# WirelessStepperMotorController.net
KiCad netlist of a schematic drawn in Altium Designer
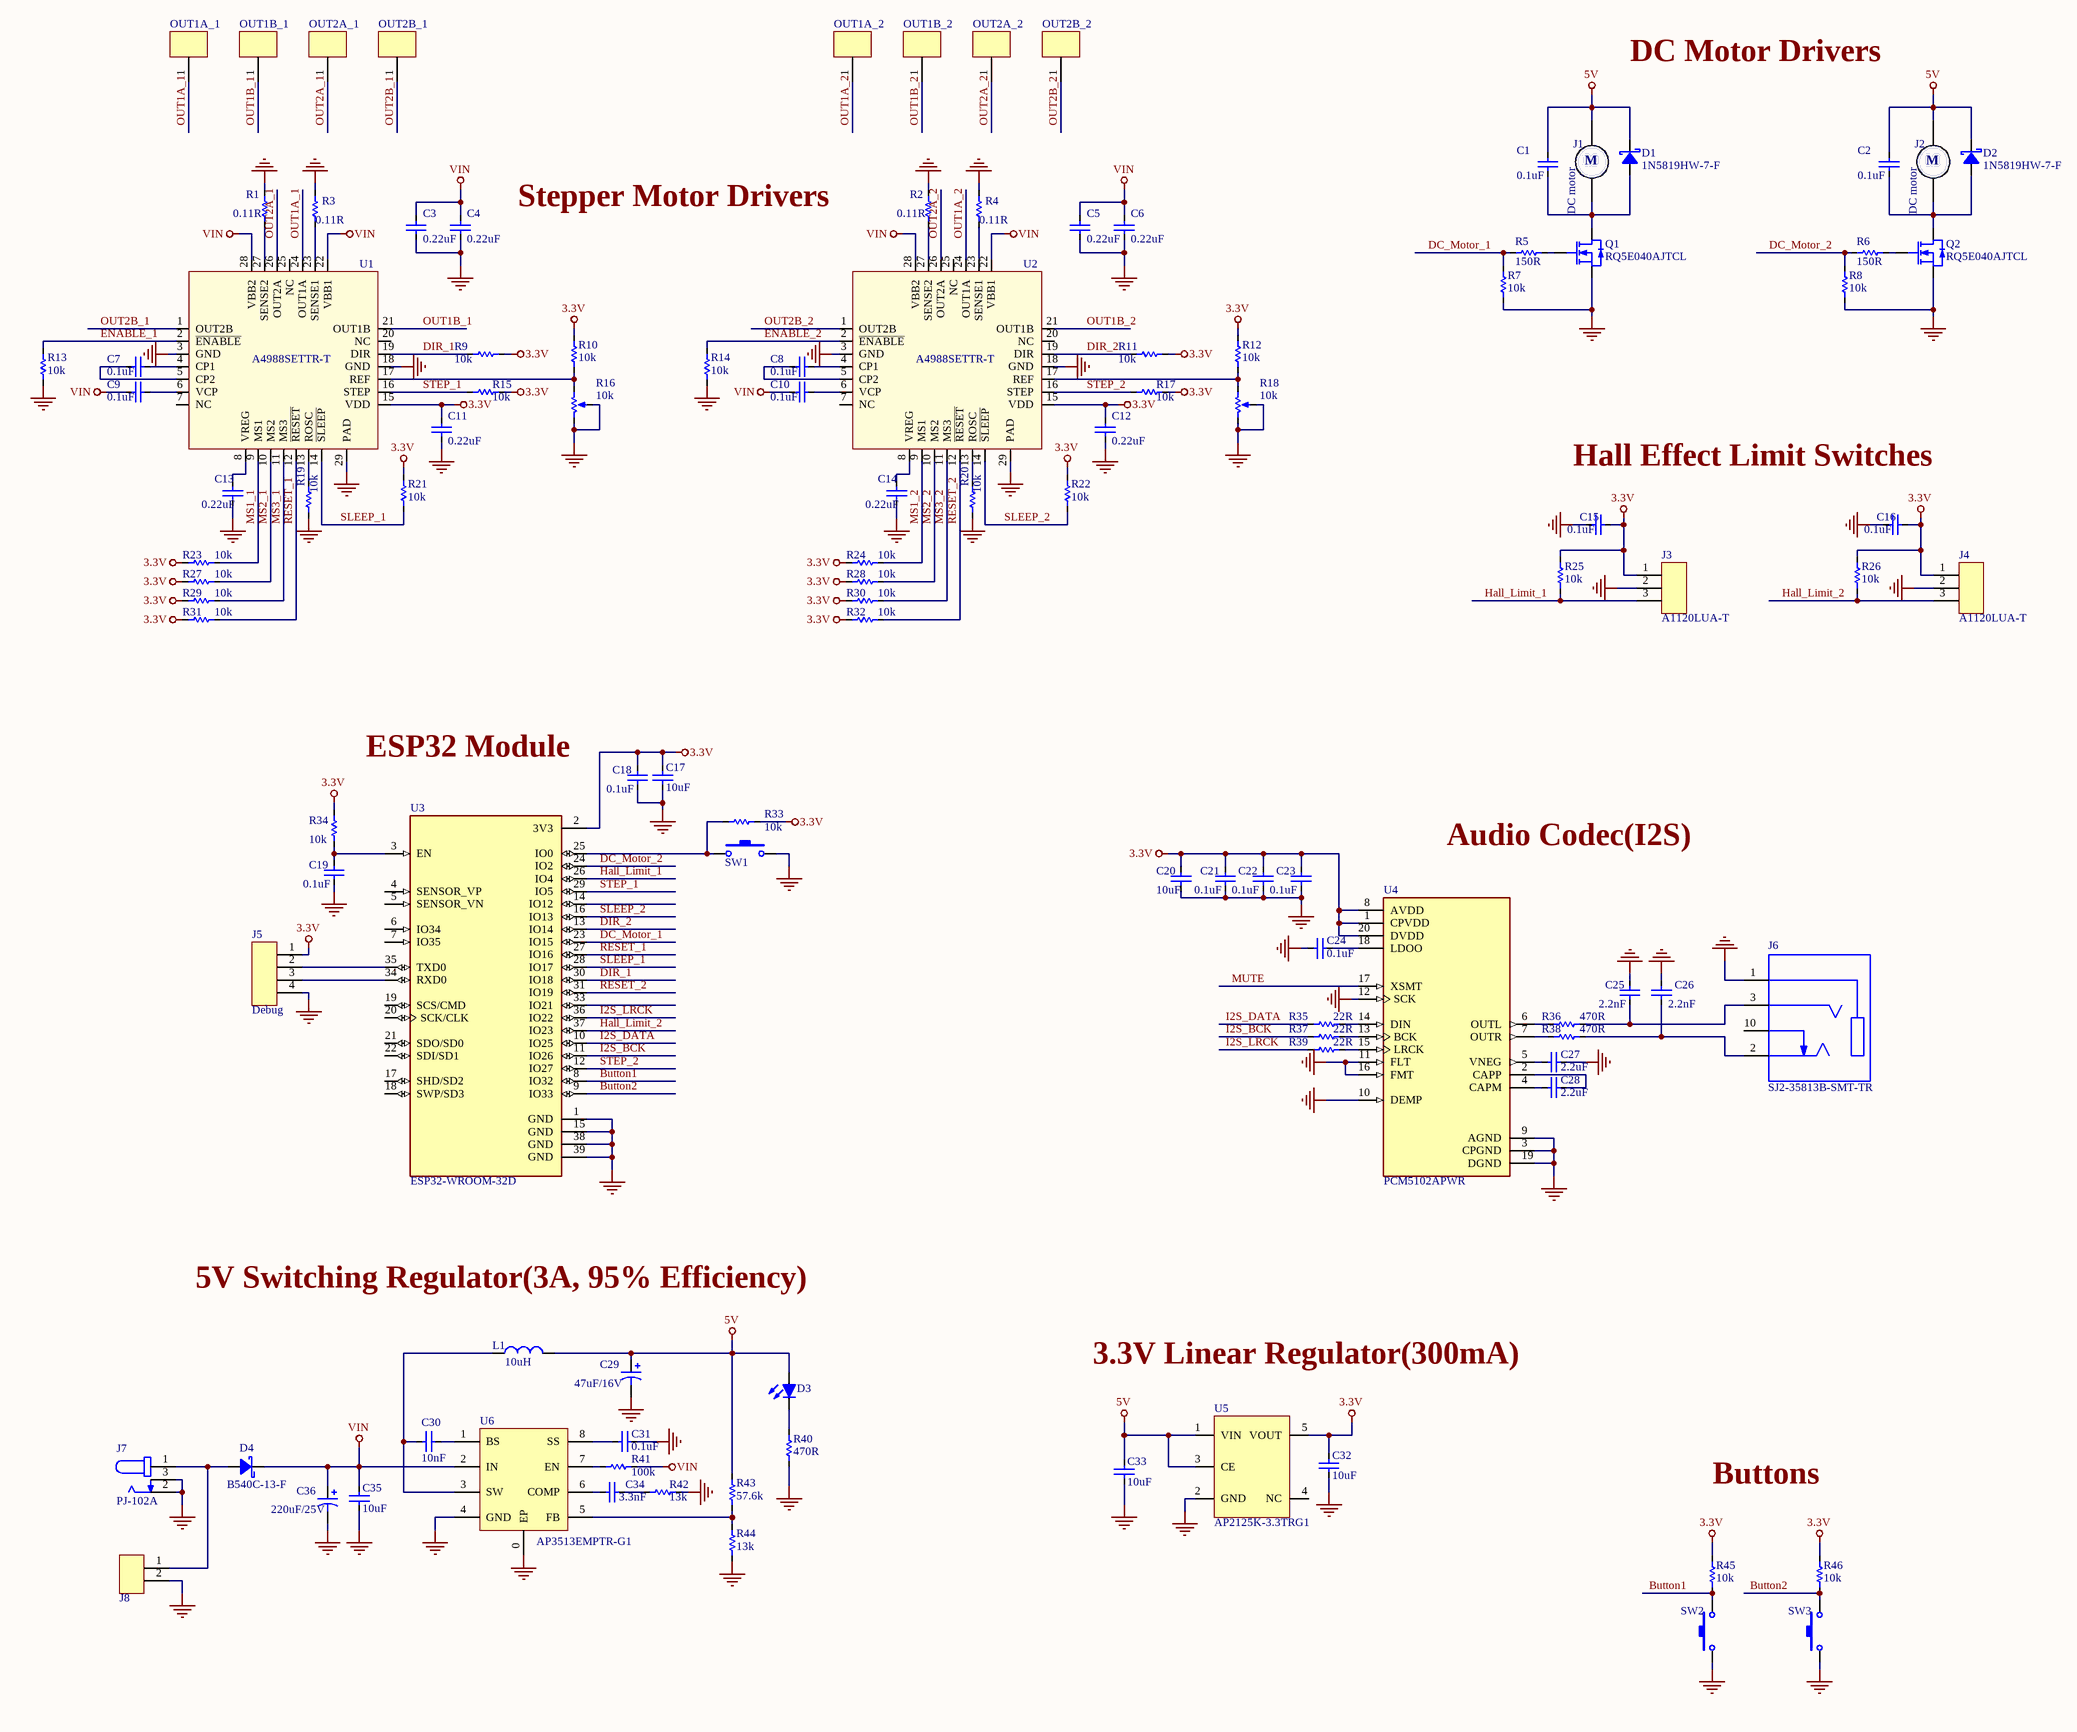
[diagram p0: WirelessStepperMotorController.SchDoc]

(export (version "E")
  (design (tool "Eeschema 10.0.6"))
  (components
    (comp (ref "C1")
      (value "0.1uF")
      (footprint "SMD_C(0603)")
      (description "0.1µF ±10% 25V")
      (fields
        (field (name "MANUFACTURER") "Yageo")
        (field (name "MANUFACTURER PART NUMBER") "CC0603KRX7R8BB104")
      )
      (libsource (lib "Miscellaneous Devices") (part "Cap"))
    )
    (comp (ref "C2")
      (value "0.1uF")
      (footprint "SMD_C(0603)")
      (description "0.1µF ±10% 25V")
      (fields
        (field (name "MANUFACTURER") "Yageo")
        (field (name "MANUFACTURER PART NUMBER") "CC0603KRX7R8BB104")
      )
      (libsource (lib "Miscellaneous Devices") (part "Cap"))
    )
    (comp (ref "C3")
      (value "0.22uF")
      (footprint "SMD_C(0603)")
      (description "0.22µF ±10% 25V")
      (fields
        (field (name "MANUFACTURER") "Yageo")
        (field (name "MANUFACTURER PART NUMBER") "CC0603KRX7R8BB224")
      )
      (libsource (lib "Miscellaneous Devices") (part "Cap"))
    )
    (comp (ref "C4")
      (value "0.22uF")
      (footprint "SMD_C(0603)")
      (description "0.22µF ±10% 25V")
      (fields
        (field (name "MANUFACTURER") "Yageo")
        (field (name "MANUFACTURER PART NUMBER") "CC0603KRX7R8BB224")
      )
      (libsource (lib "Miscellaneous Devices") (part "Cap"))
    )
    (comp (ref "C5")
      (value "0.22uF")
      (footprint "SMD_C(0603)")
      (description "0.22µF ±10% 25V")
      (fields
        (field (name "MANUFACTURER") "Yageo")
        (field (name "MANUFACTURER PART NUMBER") "CC0603KRX7R8BB224")
      )
      (libsource (lib "Miscellaneous Devices") (part "Cap"))
    )
    (comp (ref "C6")
      (value "0.22uF")
      (footprint "SMD_C(0603)")
      (description "0.22µF ±10% 25V")
      (fields
        (field (name "MANUFACTURER") "Yageo")
        (field (name "MANUFACTURER PART NUMBER") "CC0603KRX7R8BB224")
      )
      (libsource (lib "Miscellaneous Devices") (part "Cap"))
    )
    (comp (ref "C7")
      (value "0.1uF")
      (footprint "SMD_C(0603)")
      (description "0.1µF ±10% 25V")
      (fields
        (field (name "MANUFACTURER") "Yageo")
        (field (name "MANUFACTURER PART NUMBER") "CC0603KRX7R8BB104")
      )
      (libsource (lib "Miscellaneous Devices") (part "Cap"))
    )
    (comp (ref "C8")
      (value "0.1uF")
      (footprint "SMD_C(0603)")
      (description "0.1µF ±10% 25V")
      (fields
        (field (name "MANUFACTURER") "Yageo")
        (field (name "MANUFACTURER PART NUMBER") "CC0603KRX7R8BB104")
      )
      (libsource (lib "Miscellaneous Devices") (part "Cap"))
    )
    (comp (ref "C9")
      (value "0.1uF")
      (footprint "SMD_C(0603)")
      (description "0.1µF ±10% 25V")
      (fields
        (field (name "MANUFACTURER") "Yageo")
        (field (name "MANUFACTURER PART NUMBER") "CC0603KRX7R8BB104")
      )
      (libsource (lib "Miscellaneous Devices") (part "Cap"))
    )
    (comp (ref "C10")
      (value "0.1uF")
      (footprint "SMD_C(0603)")
      (description "0.1µF ±10% 25V")
      (fields
        (field (name "MANUFACTURER") "Yageo")
        (field (name "MANUFACTURER PART NUMBER") "CC0603KRX7R8BB104")
      )
      (libsource (lib "Miscellaneous Devices") (part "Cap"))
    )
    (comp (ref "C11")
      (value "0.22uF")
      (footprint "SMD_C(0603)")
      (description "0.22µF ±10% 25V")
      (fields
        (field (name "MANUFACTURER") "Yageo")
        (field (name "MANUFACTURER PART NUMBER") "CC0603KRX7R8BB224")
      )
      (libsource (lib "Miscellaneous Devices") (part "Cap"))
    )
    (comp (ref "C12")
      (value "0.22uF")
      (footprint "SMD_C(0603)")
      (description "0.22µF ±10% 25V")
      (fields
        (field (name "MANUFACTURER") "Yageo")
        (field (name "MANUFACTURER PART NUMBER") "CC0603KRX7R8BB224")
      )
      (libsource (lib "Miscellaneous Devices") (part "Cap"))
    )
    (comp (ref "C13")
      (value "0.22uF")
      (footprint "SMD_C(0603)")
      (description "0.22µF ±10% 25V")
      (fields
        (field (name "MANUFACTURER") "Yageo")
        (field (name "MANUFACTURER PART NUMBER") "CC0603KRX7R8BB224")
      )
      (libsource (lib "Miscellaneous Devices") (part "Cap"))
    )
    (comp (ref "C14")
      (value "0.22uF")
      (footprint "SMD_C(0603)")
      (description "0.22µF ±10% 25V")
      (fields
        (field (name "MANUFACTURER") "Yageo")
        (field (name "MANUFACTURER PART NUMBER") "CC0603KRX7R8BB224")
      )
      (libsource (lib "Miscellaneous Devices") (part "Cap"))
    )
    (comp (ref "C15")
      (value "0.1uF")
      (footprint "SMD_C(0603)")
      (description "0.1µF ±10% 25V")
      (fields
        (field (name "MANUFACTURER") "Yageo")
        (field (name "MANUFACTURER PART NUMBER") "CC0603KRX7R8BB104")
      )
      (libsource (lib "Miscellaneous Devices") (part "Cap"))
    )
    (comp (ref "C16")
      (value "0.1uF")
      (footprint "SMD_C(0603)")
      (description "0.1µF ±10% 25V")
      (fields
        (field (name "MANUFACTURER") "Yageo")
        (field (name "MANUFACTURER PART NUMBER") "CC0603KRX7R8BB104")
      )
      (libsource (lib "Miscellaneous Devices") (part "Cap"))
    )
    (comp (ref "C17")
      (value "10uF")
      (footprint "SMD_C(0805)")
      (description "10µF ±10% 25V")
      (fields
        (field (name "MANUFACTURER") "Murata")
        (field (name "MANUFACTURER PART NUMBER") "GRM21BR61E106KA73K")
      )
      (libsource (lib "Miscellaneous Devices") (part "Cap"))
    )
    (comp (ref "C18")
      (value "0.1uF")
      (footprint "SMD_C(0603)")
      (description "0.1µF ±10% 25V")
      (fields
        (field (name "MANUFACTURER") "Yageo")
        (field (name "MANUFACTURER PART NUMBER") "CC0603KRX7R8BB104")
      )
      (libsource (lib "Miscellaneous Devices") (part "Cap"))
    )
    (comp (ref "C19")
      (value "0.1uF")
      (footprint "SMD_C(0603)")
      (description "0.1µF ±10% 25V")
      (fields
        (field (name "MANUFACTURER") "Yageo")
        (field (name "MANUFACTURER PART NUMBER") "CC0603KRX7R8BB104")
      )
      (libsource (lib "Miscellaneous Devices") (part "Cap"))
    )
    (comp (ref "C20")
      (value "10uF")
      (footprint "SMD_C(0805)")
      (description "10µF ±10% 25V")
      (fields
        (field (name "MANUFACTURER") "Murata")
        (field (name "MANUFACTURER PART NUMBER") "GRM21BR61E106KA73K")
      )
      (libsource (lib "Miscellaneous Devices") (part "Cap"))
    )
    (comp (ref "C21")
      (value "0.1uF")
      (footprint "SMD_C(0603)")
      (description "0.1µF ±10% 25V")
      (fields
        (field (name "MANUFACTURER") "Yageo")
        (field (name "MANUFACTURER PART NUMBER") "CC0603KRX7R8BB104")
      )
      (libsource (lib "Miscellaneous Devices") (part "Cap"))
    )
    (comp (ref "C22")
      (value "0.1uF")
      (footprint "SMD_C(0603)")
      (description "0.1µF ±10% 25V")
      (fields
        (field (name "MANUFACTURER") "Yageo")
        (field (name "MANUFACTURER PART NUMBER") "CC0603KRX7R8BB104")
      )
      (libsource (lib "Miscellaneous Devices") (part "Cap"))
    )
    (comp (ref "C23")
      (value "0.1uF")
      (footprint "SMD_C(0603)")
      (description "0.1µF ±10% 25V")
      (fields
        (field (name "MANUFACTURER") "Yageo")
        (field (name "MANUFACTURER PART NUMBER") "CC0603KRX7R8BB104")
      )
      (libsource (lib "Miscellaneous Devices") (part "Cap"))
    )
    (comp (ref "C24")
      (value "0.1uF")
      (footprint "SMD_C(0603)")
      (description "0.1µF ±10% 25V")
      (fields
        (field (name "MANUFACTURER") "Yageo")
        (field (name "MANUFACTURER PART NUMBER") "CC0603KRX7R8BB104")
      )
      (libsource (lib "Miscellaneous Devices") (part "Cap"))
    )
    (comp (ref "C25")
      (value "2.2nF")
      (footprint "SMD_C(0603)")
      (description "2200pF ±10% 25V")
      (fields
        (field (name "MANUFACTURER") "Yageo")
        (field (name "MANUFACTURER PART NUMBER") "CC0603KRX7R8BB222")
      )
      (libsource (lib "Miscellaneous Devices") (part "Cap"))
    )
    (comp (ref "C26")
      (value "2.2nF")
      (footprint "SMD_C(0603)")
      (description "2200pF ±10% 25V")
      (fields
        (field (name "MANUFACTURER") "Yageo")
        (field (name "MANUFACTURER PART NUMBER") "CC0603KRX7R8BB222")
      )
      (libsource (lib "Miscellaneous Devices") (part "Cap"))
    )
    (comp (ref "C27")
      (value "2.2uF")
      (footprint "SMD_C(0603)")
      (description "2.2µF ±10% 25V")
      (fields
        (field (name "MANUFACTURER") "Yageo")
        (field (name "MANUFACTURER PART NUMBER") "CC0603KRX5R8BB225")
      )
      (libsource (lib "Miscellaneous Devices") (part "Cap"))
    )
    (comp (ref "C28")
      (value "2.2uF")
      (footprint "SMD_C(0603)")
      (description "2.2µF ±10% 25V")
      (fields
        (field (name "MANUFACTURER") "Yageo")
        (field (name "MANUFACTURER PART NUMBER") "CC0603KRX5R8BB225")
      )
      (libsource (lib "Miscellaneous Devices") (part "Cap"))
    )
    (comp (ref "C29")
      (value "47uF/16V")
      (footprint "CAPAE660X800N")
      (description "CAP ALUM 47UF 20% 16V SMD")
      (fields
        (field (name "MANUFACTURER PART NUMBER") "UWX1C470MCL1GB")
        (field (name "MANUFACTURER") "Nichicon")
      )
      (libsource (lib "Miscellaneous Devices") (part "Cap Pol1"))
    )
    (comp (ref "C30")
      (value "10nF")
      (footprint "SMD_C(0603)")
      (description "10nF ±10% 50V")
      (fields
        (field (name "MANUFACTURER") "Yageo")
        (field (name "MANUFACTURER PART NUMBER") "CC0603KPX7R9BB103")
      )
      (libsource (lib "Miscellaneous Devices") (part "Cap"))
    )
    (comp (ref "C31")
      (value "0.1uF")
      (footprint "SMD_C(0603)")
      (description "0.1µF ±10% 25V")
      (fields
        (field (name "MANUFACTURER") "Yageo")
        (field (name "MANUFACTURER PART NUMBER") "CC0603KRX7R8BB104")
      )
      (libsource (lib "Miscellaneous Devices") (part "Cap"))
    )
    (comp (ref "C32")
      (value "10uF")
      (footprint "SMD_C(0805)")
      (description "10µF ±10% 25V")
      (fields
        (field (name "MANUFACTURER") "Murata")
        (field (name "MANUFACTURER PART NUMBER") "GRM21BR61E106KA73K")
      )
      (libsource (lib "Miscellaneous Devices") (part "Cap"))
    )
    (comp (ref "C33")
      (value "10uF")
      (footprint "SMD_C(0805)")
      (description "10µF ±10% 25V")
      (fields
        (field (name "MANUFACTURER") "Murata")
        (field (name "MANUFACTURER PART NUMBER") "GRM21BR61E106KA73K")
      )
      (libsource (lib "Miscellaneous Devices") (part "Cap"))
    )
    (comp (ref "C34")
      (value "3.3nF")
      (footprint "SMD_C(0603)")
      (description "3300pF ±10% 25V")
      (fields
        (field (name "MANUFACTURER") "Yageo")
        (field (name "MANUFACTURER PART NUMBER") "CC0603KRX7R8BB332")
      )
      (libsource (lib "Miscellaneous Devices") (part "Cap"))
    )
    (comp (ref "C35")
      (value "10uF")
      (footprint "SMD_C(0805)")
      (description "10µF ±10% 25V")
      (fields
        (field (name "MANUFACTURER") "Murata")
        (field (name "MANUFACTURER PART NUMBER") "GRM21BR61E106KA73K")
      )
      (libsource (lib "Miscellaneous Devices") (part "Cap"))
    )
    (comp (ref "C36")
      (value "220uF/25V")
      (footprint "CAPAE830X1000N")
      (description "CAP ALUM 220UF 20% 25V SMD")
      (fields
        (field (name "MANUFACTURER PART NUMBER") "UUD1E221MNL1GS")
        (field (name "MANUFACTURER") "Nichicon")
      )
      (libsource (lib "Miscellaneous Devices") (part "Cap Pol1"))
    )
    (comp (ref "D1")
      (value "1N5819HW-7-F")
      (footprint "SOD-123")
      (description "DIODE SCHOTTKY 40V 1A SOD123")
      (fields (field (name "MANUFACTURER") "Diodes"))
      (libsource (lib "WirelessCharger") (part "Diode 10TQ035"))
    )
    (comp (ref "D2")
      (value "1N5819HW-7-F")
      (footprint "SOD-123")
      (description "DIODE SCHOTTKY 40V 1A SOD123")
      (fields (field (name "MANUFACTURER") "Diodes"))
      (libsource (lib "WirelessCharger") (part "Diode 10TQ035"))
    )
    (comp (ref "D3")
      (value "SML-D12U1WT86")
      (footprint "SMD_LED(0603)")
      (description "Typical RED GaAs LED")
      (fields (field (name "MANUFACTURER") "Rohm Semiconductor"))
      (libsource (lib "WirelessCharger") (part "LED1"))
    )
    (comp (ref "D4")
      (value "B540C-13-F")
      (footprint "DO-214AB")
      (description "DIODE SCHOTTKY 40V 5A SMC")
      (fields (field (name "MANUFACTURER") "Diodes"))
      (libsource (lib "WirelessCharger") (part "Diode 10TQ035"))
    )
    (comp (ref "J1")
      (value "DC motor")
      (footprint "Header-2.54m-2pin_1")
      (libsource (lib "WirelessCharger") (part "DC motor"))
    )
    (comp (ref "J2")
      (value "DC motor")
      (footprint "Header-2.54m-2pin_1")
      (libsource (lib "WirelessCharger") (part "DC motor"))
    )
    (comp (ref "J3")
      (value "A1120LUA-T")
      (footprint "Header-2.54m-3pin_1")
      (description "MAGNETIC SWITCH UNIPOLAR 3SIP")
      (fields (field (name "MANUFACTURER") "Allegro MicroSystems"))
      (libsource (lib "WirelessCharger") (part "3PinConnector"))
    )
    (comp (ref "J4")
      (value "A1120LUA-T")
      (footprint "Header-2.54m-3pin_1")
      (description "MAGNETIC SWITCH UNIPOLAR 3SIP")
      (fields (field (name "MANUFACTURER") "Allegro MicroSystems"))
      (libsource (lib "WirelessCharger") (part "3PinConnector"))
    )
    (comp (ref "J5")
      (value "Debug")
      (footprint "Header-2.54m-4pin")
      (description "4PinConnector")
      (libsource (lib "WirelessCharger") (part "4PinConnector"))
    )
    (comp (ref "J6")
      (value "SJ2-35813B-SMT-TR")
      (footprint "CUI_SJ2-35813B-SMT-TR")
      (description "AUDIO JACK, 3.5 MM, RT, 3 CONDUC")
      (fields (field (name "MANUFACTURER") "CUI Devices"))
      (libsource (lib "WirelessCharger") (part "SJ2-35813B-SMT-TR"))
    )
    (comp (ref "J7")
      (value "PJ-102A")
      (footprint "CUI_PJ-102A")
      (description "CONN PWR JACK 2X5.5MM SOLDER")
      (fields (field (name "MANUFACTURER") "CUI Devices"))
      (libsource (lib "WirelessCharger") (part "PJ-102A"))
    )
    (comp (ref "J8")
      (value "2 Pin Connector")
      (footprint "Header-2.54m-2pin_2")
      (libsource (lib "WirelessCharger") (part "2PinConnector"))
    )
    (comp (ref "L1")
      (value "10uH")
      (footprint "IND_NRS5040")
      (description "FIXED IND 10UH 2.1A 72.8 MOHM")
      (fields
        (field (name "MANUFACTURER PART NUMBER") "NRS5040T100MMGJ")
        (field (name "MANUFACTURER") "Taiyo Yuden")
      )
      (libsource (lib "WirelessCharger") (part "Inductor"))
    )
    (comp (ref "OUT1A_1")
      (value "Terminal")
      (footprint "Header-2.54m-1pin")
      (libsource (lib "WirelessCharger") (part "Terminal"))
    )
    (comp (ref "OUT1A_2")
      (value "Terminal")
      (footprint "Header-2.54m-1pin")
      (libsource (lib "WirelessCharger") (part "Terminal"))
    )
    (comp (ref "OUT1B_1")
      (value "Terminal")
      (footprint "Header-2.54m-1pin")
      (libsource (lib "WirelessCharger") (part "Terminal"))
    )
    (comp (ref "OUT1B_2")
      (value "Terminal")
      (footprint "Header-2.54m-1pin")
      (libsource (lib "WirelessCharger") (part "Terminal"))
    )
    (comp (ref "OUT2A_1")
      (value "Terminal")
      (footprint "Header-2.54m-1pin")
      (libsource (lib "WirelessCharger") (part "Terminal"))
    )
    (comp (ref "OUT2A_2")
      (value "Terminal")
      (footprint "Header-2.54m-1pin")
      (libsource (lib "WirelessCharger") (part "Terminal"))
    )
    (comp (ref "OUT2B_1")
      (value "Terminal")
      (footprint "Header-2.54m-1pin")
      (libsource (lib "WirelessCharger") (part "Terminal"))
    )
    (comp (ref "OUT2B_2")
      (value "Terminal")
      (footprint "Header-2.54m-1pin")
      (libsource (lib "WirelessCharger") (part "Terminal"))
    )
    (comp (ref "Q1")
      (value "RQ5E040AJTCL")
      (footprint "SC-96")
      (description "MOSFET N-CH 30V 4A TSMT3")
      (fields (field (name "MANUFACTURER") "Rohm Semiconductor"))
      (libsource (lib "BidirectionalCharger") (part "MOSFET-N"))
    )
    (comp (ref "Q2")
      (value "RQ5E040AJTCL")
      (footprint "SC-96")
      (description "MOSFET N-CH 30V 4A TSMT3")
      (fields (field (name "MANUFACTURER") "Rohm Semiconductor"))
      (libsource (lib "BidirectionalCharger") (part "MOSFET-N"))
    )
    (comp (ref "R1")
      (value "0.11R")
      (footprint "SMD_R(1206)")
      (description "110 mOhms ±1% 0.25W")
      (fields
        (field (name "MANUFACTURER") "Yageo")
        (field (name "MANUFACTURER PART NUMBER") "RL1206FR-070R11L")
      )
      (libsource (lib "Miscellaneous Devices") (part "Res Semi"))
    )
    (comp (ref "R2")
      (value "0.11R")
      (footprint "SMD_R(1206)")
      (description "110 mOhms ±1% 0.25W")
      (fields
        (field (name "MANUFACTURER") "Yageo")
        (field (name "MANUFACTURER PART NUMBER") "RL1206FR-070R11L")
      )
      (libsource (lib "Miscellaneous Devices") (part "Res Semi"))
    )
    (comp (ref "R3")
      (value "0.11R")
      (footprint "SMD_R(1206)")
      (description "110 mOhms ±1% 0.25W")
      (fields
        (field (name "MANUFACTURER") "Yageo")
        (field (name "MANUFACTURER PART NUMBER") "RL1206FR-070R11L")
      )
      (libsource (lib "Miscellaneous Devices") (part "Res Semi"))
    )
    (comp (ref "R4")
      (value "0.11R")
      (footprint "SMD_R(1206)")
      (description "110 mOhms ±1% 0.25W")
      (fields
        (field (name "MANUFACTURER") "Yageo")
        (field (name "MANUFACTURER PART NUMBER") "RL1206FR-070R11L")
      )
      (libsource (lib "Miscellaneous Devices") (part "Res Semi"))
    )
    (comp (ref "R5")
      (value "150R")
      (footprint "SMD_R(0603)")
      (description "150 Ohms ±1% 0.1W")
      (fields
        (field (name "MANUFACTURER") "Yageo")
        (field (name "MANUFACTURER PART NUMBER") "RC0603FR-07150RL")
      )
      (libsource (lib "Miscellaneous Devices") (part "Res Semi"))
    )
    (comp (ref "R6")
      (value "150R")
      (footprint "SMD_R(0603)")
      (description "150 Ohms ±1% 0.1W")
      (fields
        (field (name "MANUFACTURER") "Yageo")
        (field (name "MANUFACTURER PART NUMBER") "RC0603FR-07150RL")
      )
      (libsource (lib "Miscellaneous Devices") (part "Res Semi"))
    )
    (comp (ref "R7")
      (value "10k")
      (footprint "SMD_R(0603)")
      (description "10 kOhms ±1% 0.1W")
      (fields
        (field (name "MANUFACTURER") "Yageo")
        (field (name "MANUFACTURER PART NUMBER") "RC0603FR-0710KL")
      )
      (libsource (lib "Miscellaneous Devices") (part "Res Semi"))
    )
    (comp (ref "R8")
      (value "10k")
      (footprint "SMD_R(0603)")
      (description "10 kOhms ±1% 0.1W")
      (fields
        (field (name "MANUFACTURER") "Yageo")
        (field (name "MANUFACTURER PART NUMBER") "RC0603FR-0710KL")
      )
      (libsource (lib "Miscellaneous Devices") (part "Res Semi"))
    )
    (comp (ref "R9")
      (value "10k")
      (footprint "SMD_R(0603)")
      (description "10 kOhms ±1% 0.1W")
      (fields
        (field (name "MANUFACTURER") "Yageo")
        (field (name "MANUFACTURER PART NUMBER") "RC0603FR-0710KL")
      )
      (libsource (lib "Miscellaneous Devices") (part "Res Semi"))
    )
    (comp (ref "R10")
      (value "10k")
      (footprint "SMD_R(0603)")
      (description "10 kOhms ±1% 0.1W")
      (fields
        (field (name "MANUFACTURER") "Yageo")
        (field (name "MANUFACTURER PART NUMBER") "RC0603FR-0710KL")
      )
      (libsource (lib "Miscellaneous Devices") (part "Res Semi"))
    )
    (comp (ref "R11")
      (value "10k")
      (footprint "SMD_R(0603)")
      (description "10 kOhms ±1% 0.1W")
      (fields
        (field (name "MANUFACTURER") "Yageo")
        (field (name "MANUFACTURER PART NUMBER") "RC0603FR-0710KL")
      )
      (libsource (lib "Miscellaneous Devices") (part "Res Semi"))
    )
    (comp (ref "R12")
      (value "10k")
      (footprint "SMD_R(0603)")
      (description "10 kOhms ±1% 0.1W")
      (fields
        (field (name "MANUFACTURER") "Yageo")
        (field (name "MANUFACTURER PART NUMBER") "RC0603FR-0710KL")
      )
      (libsource (lib "Miscellaneous Devices") (part "Res Semi"))
    )
    (comp (ref "R13")
      (value "10k")
      (footprint "SMD_R(0603)")
      (description "10 kOhms ±1% 0.1W")
      (fields
        (field (name "MANUFACTURER") "Yageo")
        (field (name "MANUFACTURER PART NUMBER") "RC0603FR-0710KL")
      )
      (libsource (lib "Miscellaneous Devices") (part "Res Semi"))
    )
    (comp (ref "R14")
      (value "10k")
      (footprint "SMD_R(0603)")
      (description "10 kOhms ±1% 0.1W")
      (fields
        (field (name "MANUFACTURER") "Yageo")
        (field (name "MANUFACTURER PART NUMBER") "RC0603FR-0710KL")
      )
      (libsource (lib "Miscellaneous Devices") (part "Res Semi"))
    )
    (comp (ref "R15")
      (value "10k")
      (footprint "SMD_R(0603)")
      (description "10 kOhms ±1% 0.1W")
      (fields
        (field (name "MANUFACTURER") "Yageo")
        (field (name "MANUFACTURER PART NUMBER") "RC0603FR-0710KL")
      )
      (libsource (lib "Miscellaneous Devices") (part "Res Semi"))
    )
    (comp (ref "R16")
      (value "10k")
      (footprint "TRIM_TC33X-2-103E")
      (description "Potentiometer")
      (fields (field (name "MANUFACTURER PART NUMBER") "TC33X-2-103E") (field (name "MANUFACTURER") "Bourns"))
      (libsource (lib "Miscellaneous Devices") (part "RPot"))
    )
    (comp (ref "R17")
      (value "10k")
      (footprint "SMD_R(0603)")
      (description "10 kOhms ±1% 0.1W")
      (fields
        (field (name "MANUFACTURER") "Yageo")
        (field (name "MANUFACTURER PART NUMBER") "RC0603FR-0710KL")
      )
      (libsource (lib "Miscellaneous Devices") (part "Res Semi"))
    )
    (comp (ref "R18")
      (value "10k")
      (footprint "TRIM_TC33X-2-103E")
      (description "Potentiometer")
      (fields (field (name "MANUFACTURER PART NUMBER") "TC33X-2-103E") (field (name "MANUFACTURER") "Bourns"))
      (libsource (lib "Miscellaneous Devices") (part "RPot"))
    )
    (comp (ref "R19")
      (value "10k")
      (footprint "SMD_R(0603)")
      (description "10 kOhms ±1% 0.1W")
      (fields
        (field (name "MANUFACTURER") "Yageo")
        (field (name "MANUFACTURER PART NUMBER") "RC0603FR-0710KL")
      )
      (libsource (lib "Miscellaneous Devices") (part "Res Semi"))
    )
    (comp (ref "R20")
      (value "10k")
      (footprint "SMD_R(0603)")
      (description "10 kOhms ±1% 0.1W")
      (fields
        (field (name "MANUFACTURER") "Yageo")
        (field (name "MANUFACTURER PART NUMBER") "RC0603FR-0710KL")
      )
      (libsource (lib "Miscellaneous Devices") (part "Res Semi"))
    )
    (comp (ref "R21")
      (value "10k")
      (footprint "SMD_R(0603)")
      (description "10 kOhms ±1% 0.1W")
      (fields
        (field (name "MANUFACTURER") "Yageo")
        (field (name "MANUFACTURER PART NUMBER") "RC0603FR-0710KL")
      )
      (libsource (lib "Miscellaneous Devices") (part "Res Semi"))
    )
    (comp (ref "R22")
      (value "10k")
      (footprint "SMD_R(0603)")
      (description "10 kOhms ±1% 0.1W")
      (fields
        (field (name "MANUFACTURER") "Yageo")
        (field (name "MANUFACTURER PART NUMBER") "RC0603FR-0710KL")
      )
      (libsource (lib "Miscellaneous Devices") (part "Res Semi"))
    )
    (comp (ref "R23")
      (value "10k")
      (footprint "SMD_R(0603)")
      (description "10 kOhms ±1% 0.1W")
      (fields
        (field (name "MANUFACTURER") "Yageo")
        (field (name "MANUFACTURER PART NUMBER") "RC0603FR-0710KL")
      )
      (libsource (lib "Miscellaneous Devices") (part "Res Semi"))
    )
    (comp (ref "R24")
      (value "10k")
      (footprint "SMD_R(0603)")
      (description "10 kOhms ±1% 0.1W")
      (fields
        (field (name "MANUFACTURER") "Yageo")
        (field (name "MANUFACTURER PART NUMBER") "RC0603FR-0710KL")
      )
      (libsource (lib "Miscellaneous Devices") (part "Res Semi"))
    )
    (comp (ref "R25")
      (value "10k")
      (footprint "SMD_R(0603)")
      (description "10 kOhms ±1% 0.1W")
      (fields
        (field (name "MANUFACTURER") "Yageo")
        (field (name "MANUFACTURER PART NUMBER") "RC0603FR-0710KL")
      )
      (libsource (lib "Miscellaneous Devices") (part "Res Semi"))
    )
    (comp (ref "R26")
      (value "10k")
      (footprint "SMD_R(0603)")
      (description "10 kOhms ±1% 0.1W")
      (fields
        (field (name "MANUFACTURER") "Yageo")
        (field (name "MANUFACTURER PART NUMBER") "RC0603FR-0710KL")
      )
      (libsource (lib "Miscellaneous Devices") (part "Res Semi"))
    )
    (comp (ref "R27")
      (value "10k")
      (footprint "SMD_R(0603)")
      (description "10 kOhms ±1% 0.1W")
      (fields
        (field (name "MANUFACTURER") "Yageo")
        (field (name "MANUFACTURER PART NUMBER") "RC0603FR-0710KL")
      )
      (libsource (lib "Miscellaneous Devices") (part "Res Semi"))
    )
    (comp (ref "R28")
      (value "10k")
      (footprint "SMD_R(0603)")
      (description "10 kOhms ±1% 0.1W")
      (fields
        (field (name "MANUFACTURER") "Yageo")
        (field (name "MANUFACTURER PART NUMBER") "RC0603FR-0710KL")
      )
      (libsource (lib "Miscellaneous Devices") (part "Res Semi"))
    )
    (comp (ref "R29")
      (value "10k")
      (footprint "SMD_R(0603)")
      (description "10 kOhms ±1% 0.1W")
      (fields
        (field (name "MANUFACTURER") "Yageo")
        (field (name "MANUFACTURER PART NUMBER") "RC0603FR-0710KL")
      )
      (libsource (lib "Miscellaneous Devices") (part "Res Semi"))
    )
    (comp (ref "R30")
      (value "10k")
      (footprint "SMD_R(0603)")
      (description "10 kOhms ±1% 0.1W")
      (fields
        (field (name "MANUFACTURER") "Yageo")
        (field (name "MANUFACTURER PART NUMBER") "RC0603FR-0710KL")
      )
      (libsource (lib "Miscellaneous Devices") (part "Res Semi"))
    )
    (comp (ref "R31")
      (value "10k")
      (footprint "SMD_R(0603)")
      (description "10 kOhms ±1% 0.1W")
      (fields
        (field (name "MANUFACTURER") "Yageo")
        (field (name "MANUFACTURER PART NUMBER") "RC0603FR-0710KL")
      )
      (libsource (lib "Miscellaneous Devices") (part "Res Semi"))
    )
    (comp (ref "R32")
      (value "10k")
      (footprint "SMD_R(0603)")
      (description "10 kOhms ±1% 0.1W")
      (fields
        (field (name "MANUFACTURER") "Yageo")
        (field (name "MANUFACTURER PART NUMBER") "RC0603FR-0710KL")
      )
      (libsource (lib "Miscellaneous Devices") (part "Res Semi"))
    )
    (comp (ref "R33")
      (value "10k")
      (footprint "SMD_R(0603)")
      (description "10 kOhms ±1% 0.1W")
      (fields
        (field (name "MANUFACTURER") "Yageo")
        (field (name "MANUFACTURER PART NUMBER") "RC0603FR-0710KL")
      )
      (libsource (lib "Miscellaneous Devices") (part "Res Semi"))
    )
    (comp (ref "R34")
      (value "10k")
      (footprint "SMD_R(0603)")
      (description "10 kOhms ±1% 0.1W")
      (fields
        (field (name "MANUFACTURER") "Yageo")
        (field (name "MANUFACTURER PART NUMBER") "RC0603FR-0710KL")
      )
      (libsource (lib "Miscellaneous Devices") (part "Res Semi"))
    )
    (comp (ref "R35")
      (value "22R")
      (footprint "SMD_R(0603)")
      (description "22 Ohms ±1% 0.1W")
      (fields
        (field (name "MANUFACTURER") "Yageo")
        (field (name "MANUFACTURER PART NUMBER") "RC0603FR-0722RL")
      )
      (libsource (lib "Miscellaneous Devices") (part "Res Semi"))
    )
    (comp (ref "R36")
      (value "470R")
      (footprint "SMD_R(0603)")
      (description "470 Ohms ±1% 0.1W")
      (fields
        (field (name "MANUFACTURER") "Yageo")
        (field (name "MANUFACTURER PART NUMBER") "RC0603FR-07470RL")
      )
      (libsource (lib "Miscellaneous Devices") (part "Res Semi"))
    )
    (comp (ref "R37")
      (value "22R")
      (footprint "SMD_R(0603)")
      (description "22 Ohms ±1% 0.1W")
      (fields
        (field (name "MANUFACTURER") "Yageo")
        (field (name "MANUFACTURER PART NUMBER") "RC0603FR-0722RL")
      )
      (libsource (lib "Miscellaneous Devices") (part "Res Semi"))
    )
    (comp (ref "R38")
      (value "470R")
      (footprint "SMD_R(0603)")
      (description "470 Ohms ±1% 0.1W")
      (fields
        (field (name "MANUFACTURER") "Yageo")
        (field (name "MANUFACTURER PART NUMBER") "RC0603FR-07470RL")
      )
      (libsource (lib "Miscellaneous Devices") (part "Res Semi"))
    )
    (comp (ref "R39")
      (value "22R")
      (footprint "SMD_R(0603)")
      (description "22 Ohms ±1% 0.1W")
      (fields
        (field (name "MANUFACTURER") "Yageo")
        (field (name "MANUFACTURER PART NUMBER") "RC0603FR-0722RL")
      )
      (libsource (lib "Miscellaneous Devices") (part "Res Semi"))
    )
    (comp (ref "R40")
      (value "470R")
      (footprint "SMD_R(0603)")
      (description "470 Ohms ±1% 0.1W")
      (fields
        (field (name "MANUFACTURER") "Yageo")
        (field (name "MANUFACTURER PART NUMBER") "RC0603FR-07470RL")
      )
      (libsource (lib "Miscellaneous Devices") (part "Res Semi"))
    )
    (comp (ref "R41")
      (value "100k")
      (footprint "SMD_R(0603)")
      (description "10 kOhms ±1% 0.1W")
      (fields
        (field (name "MANUFACTURER") "Yageo")
        (field (name "MANUFACTURER PART NUMBER") "RC0603FR-07100KL")
      )
      (libsource (lib "Miscellaneous Devices") (part "Res Semi"))
    )
    (comp (ref "R42")
      (value "13k")
      (footprint "SMD_R(0603)")
      (description "13 kOhms ±1% 0.1W")
      (fields
        (field (name "MANUFACTURER") "Yageo")
        (field (name "MANUFACTURER PART NUMBER") "RC0603FR-0713KL")
      )
      (libsource (lib "Miscellaneous Devices") (part "Res Semi"))
    )
    (comp (ref "R43")
      (value "57.6k")
      (footprint "SMD_R(0603)")
      (description "93.1kOhms ±1% 0.1W")
      (fields
        (field (name "MANUFACTURER") "Yageo")
        (field (name "MANUFACTURER PART NUMBER") "RC0603FR-0757K6L")
      )
      (libsource (lib "Miscellaneous Devices") (part "Res Semi"))
    )
    (comp (ref "R44")
      (value "13k")
      (footprint "SMD_R(0603)")
      (description "13kOhms ±1% 0.1W")
      (fields
        (field (name "MANUFACTURER") "Yageo")
        (field (name "MANUFACTURER PART NUMBER") "RC0603FR-0713KL")
      )
      (libsource (lib "Miscellaneous Devices") (part "Res Semi"))
    )
    (comp (ref "R45")
      (value "10k")
      (footprint "SMD_R(0603)")
      (description "10 kOhms ±1% 0.1W")
      (fields
        (field (name "MANUFACTURER") "Yageo")
        (field (name "MANUFACTURER PART NUMBER") "RC0603FR-0710KL")
      )
      (libsource (lib "Miscellaneous Devices") (part "Res Semi"))
    )
    (comp (ref "R46")
      (value "10k")
      (footprint "SMD_R(0603)")
      (description "10 kOhms ±1% 0.1W")
      (fields
        (field (name "MANUFACTURER") "Yageo")
        (field (name "MANUFACTURER PART NUMBER") "RC0603FR-0710KL")
      )
      (libsource (lib "Miscellaneous Devices") (part "Res Semi"))
    )
    (comp (ref "SW1")
      (value "TL1015AF160QG")
      (footprint "SW_TL1015AF160QG")
      (description "SWITCH TACTILE SPST-NO 0.05A 12V")
      (fields (field (name "MANUFACTURER") "E-Switch"))
      (libsource (lib "Miscellaneous Devices") (part "SW-PB"))
    )
    (comp (ref "SW2")
      (value "TL1015AF160QG")
      (footprint "SW_TL1015AF160QG")
      (description "SWITCH TACTILE SPST-NO 0.05A 12V")
      (fields (field (name "MANUFACTURER") "E-Switch"))
      (libsource (lib "Miscellaneous Devices") (part "SW-PB"))
    )
    (comp (ref "SW3")
      (value "TL1015AF160QG")
      (footprint "SW_TL1015AF160QG")
      (description "SWITCH TACTILE SPST-NO 0.05A 12V")
      (fields (field (name "MANUFACTURER") "E-Switch"))
      (libsource (lib "Miscellaneous Devices") (part "SW-PB"))
    )
    (comp (ref "U1")
      (value "A4988SETTR-T")
      (footprint "QFN28G_0.5-5X5MM")
      (description "Bipolar Motor Driver DMOS Logic 28-QFN _5x5_")
      (fields (field (name "MANUFACTURER") "Allegro MicroSystems LLC"))
      (libsource (lib "WirelessCharger") (part "DRIVER-A4988SETTR-T(QFN28)"))
    )
    (comp (ref "U2")
      (value "A4988SETTR-T")
      (footprint "QFN28G_0.5-5X5MM")
      (description "Bipolar Motor Driver DMOS Logic 28-QFN _5x5_")
      (fields (field (name "MANUFACTURER") "Allegro MicroSystems LLC"))
      (libsource (lib "WirelessCharger") (part "DRIVER-A4988SETTR-T(QFN28)"))
    )
    (comp (ref "U3")
      (value "ESP32-WROOM-32D")
      (footprint "MODULE_ESP32-WROOM-32D")
      (fields (field (name "MANUFACTURER") "Espressif Systems"))
      (libsource (lib "WirelessCharger") (part "ESP32-WROOM-32D"))
    )
    (comp (ref "U4")
      (value "PCM5102APWR")
      (footprint "TSSOP-20N")
      (description "2VRMS DirectPath, 112dB Audio Stereo DAC with 32-bit, 384kHz PCM Interface 20-TSSOP -25 to 85")
      (fields (field (name "MANUFACTURER") "Texas Instruments"))
      (libsource (lib "WirelessCharger") (part "PCM5102APWR"))
    )
    (comp (ref "U5")
      (value "AP2125K-3.3TRG1")
      (footprint "SOT23-5")
      (description "IC REG LINEAR 2.8V 300MA SOT23-5")
      (fields (field (name "MANUFACTURER") "Diodes Incorporated"))
      (libsource (lib "WirelessCharger") (part "AP2125K-2.8TRG1"))
    )
    (comp (ref "U6")
      (value "AP3513EMPTR-G1")
      (footprint "SOIC-8(EP)")
      (description "IC REG BUCK ADJUSTABLE 3A 8SO")
      (fields (field (name "MANUFACTURER") "Diodes"))
      (libsource (lib "WirelessCharger") (part "AP3513EMPTR-G1"))
    )
  )
  (nets
    (net (code "1") (name "/Button1") (class "Default")
      (node (ref "R45") (pin "1") (pinfunction "1_1") (pintype "passive"))
      (node (ref "SW2") (pin "2") (pinfunction "2_2") (pintype "passive"))
      (node (ref "U3") (pin "8") (pinfunction "IO32_8") (pintype "bidirectional"))
    )
    (net (code "2") (name "/Button2") (class "Default")
      (node (ref "R46") (pin "1") (pinfunction "1_1") (pintype "passive"))
      (node (ref "SW3") (pin "2") (pinfunction "2_2") (pintype "passive"))
      (node (ref "U3") (pin "9") (pinfunction "IO33_9") (pintype "bidirectional"))
    )
    (net (code "3") (name "/DC_Motor_1") (class "Default")
      (node (ref "R5") (pin "1") (pinfunction "1_1") (pintype "passive"))
      (node (ref "R7") (pin "1") (pinfunction "1_1") (pintype "passive"))
      (node (ref "U3") (pin "23") (pinfunction "IO15_23") (pintype "bidirectional"))
    )
    (net (code "4") (name "/DC_Motor_2") (class "Default")
      (node (ref "R6") (pin "1") (pinfunction "1_1") (pintype "passive"))
      (node (ref "R8") (pin "1") (pinfunction "1_1") (pintype "passive"))
      (node (ref "U3") (pin "24") (pinfunction "IO2_24") (pintype "bidirectional"))
    )
    (net (code "5") (name "/DIR_1") (class "Default")
      (node (ref "R9") (pin "1") (pinfunction "1_1") (pintype "passive"))
      (node (ref "U1") (pin "19") (pinfunction "DIR_19") (pintype "passive"))
      (node (ref "U3") (pin "30") (pinfunction "IO18_30") (pintype "bidirectional"))
    )
    (net (code "6") (name "/DIR_2") (class "Default")
      (node (ref "R11") (pin "1") (pinfunction "1_1") (pintype "passive"))
      (node (ref "U2") (pin "19") (pinfunction "DIR_19") (pintype "passive"))
      (node (ref "U3") (pin "13") (pinfunction "IO14_13") (pintype "bidirectional"))
    )
    (net (code "7") (name "/ENABLE_1") (class "Default")
      (node (ref "R13") (pin "2") (pinfunction "2_2") (pintype "passive"))
      (node (ref "U1") (pin "2") (pinfunction "~{ENABLE}_2") (pintype "passive"))
    )
    (net (code "8") (name "/ENABLE_2") (class "Default")
      (node (ref "R14") (pin "2") (pinfunction "2_2") (pintype "passive"))
      (node (ref "U2") (pin "2") (pinfunction "~{ENABLE}_2") (pintype "passive"))
    )
    (net (code "9") (name "/Hall_Limit_1") (class "Default")
      (node (ref "J3") (pin "3") (pinfunction "3_3") (pintype "passive"))
      (node (ref "R25") (pin "2") (pinfunction "2_2") (pintype "passive"))
      (node (ref "U3") (pin "26") (pinfunction "IO4_26") (pintype "bidirectional"))
    )
    (net (code "10") (name "/Hall_Limit_2") (class "Default")
      (node (ref "J4") (pin "3") (pinfunction "3_3") (pintype "passive"))
      (node (ref "R26") (pin "2") (pinfunction "2_2") (pintype "passive"))
      (node (ref "U3") (pin "37") (pinfunction "IO23_37") (pintype "bidirectional"))
    )
    (net (code "11") (name "/I2S_BCK") (class "Default")
      (node (ref "R37") (pin "1") (pinfunction "1_1") (pintype "passive"))
      (node (ref "U3") (pin "11") (pinfunction "IO26_11") (pintype "bidirectional"))
    )
    (net (code "12") (name "/I2S_DATA") (class "Default")
      (node (ref "R35") (pin "1") (pinfunction "1_1") (pintype "passive"))
      (node (ref "U3") (pin "10") (pinfunction "IO25_10") (pintype "bidirectional"))
    )
    (net (code "13") (name "/I2S_LRCK") (class "Default")
      (node (ref "R39") (pin "1") (pinfunction "1_1") (pintype "passive"))
      (node (ref "U3") (pin "36") (pinfunction "IO22_36") (pintype "bidirectional"))
    )
    (net (code "14") (name "/MS1_1") (class "Default")
      (node (ref "R23") (pin "1") (pinfunction "1_1") (pintype "passive"))
      (node (ref "U1") (pin "9") (pinfunction "MS1_9") (pintype "passive"))
    )
    (net (code "15") (name "/MS1_2") (class "Default")
      (node (ref "R24") (pin "1") (pinfunction "1_1") (pintype "passive"))
      (node (ref "U2") (pin "9") (pinfunction "MS1_9") (pintype "passive"))
    )
    (net (code "16") (name "/MS2_1") (class "Default")
      (node (ref "R27") (pin "1") (pinfunction "1_1") (pintype "passive"))
      (node (ref "U1") (pin "10") (pinfunction "MS2_10") (pintype "passive"))
    )
    (net (code "17") (name "/MS2_2") (class "Default")
      (node (ref "R28") (pin "1") (pinfunction "1_1") (pintype "passive"))
      (node (ref "U2") (pin "10") (pinfunction "MS2_10") (pintype "passive"))
    )
    (net (code "18") (name "/MS3_1") (class "Default")
      (node (ref "R29") (pin "1") (pinfunction "1_1") (pintype "passive"))
      (node (ref "U1") (pin "11") (pinfunction "MS3_11") (pintype "passive"))
    )
    (net (code "19") (name "/MS3_2") (class "Default")
      (node (ref "R30") (pin "1") (pinfunction "1_1") (pintype "passive"))
      (node (ref "U2") (pin "11") (pinfunction "MS3_11") (pintype "passive"))
    )
    (net (code "20") (name "/MUTE") (class "Default")
      (node (ref "U4") (pin "17") (pinfunction "XSMT_17") (pintype "input"))
    )
    (net (code "21") (name "/OUT1A_1") (class "Default")
      (node (ref "OUT1A_1") (pin "1") (pinfunction "1_1") (pintype "passive"))
      (node (ref "U1") (pin "24") (pinfunction "OUT1A_24") (pintype "passive"))
    )
    (net (code "22") (name "/OUT1A_2") (class "Default")
      (node (ref "OUT1A_2") (pin "1") (pinfunction "1_1") (pintype "passive"))
      (node (ref "U2") (pin "24") (pinfunction "OUT1A_24") (pintype "passive"))
    )
    (net (code "23") (name "/OUT1B_1") (class "Default")
      (node (ref "OUT1B_1") (pin "1") (pinfunction "1_1") (pintype "passive"))
      (node (ref "U1") (pin "21") (pinfunction "OUT1B_21") (pintype "passive"))
    )
    (net (code "24") (name "/OUT1B_2") (class "Default")
      (node (ref "OUT1B_2") (pin "1") (pinfunction "1_1") (pintype "passive"))
      (node (ref "U2") (pin "21") (pinfunction "OUT1B_21") (pintype "passive"))
    )
    (net (code "25") (name "/OUT2A_1") (class "Default")
      (node (ref "OUT2A_1") (pin "1") (pinfunction "1_1") (pintype "passive"))
      (node (ref "U1") (pin "26") (pinfunction "OUT2A_26") (pintype "passive"))
    )
    (net (code "26") (name "/OUT2A_2") (class "Default")
      (node (ref "OUT2A_2") (pin "1") (pinfunction "1_1") (pintype "passive"))
      (node (ref "U2") (pin "26") (pinfunction "OUT2A_26") (pintype "passive"))
    )
    (net (code "27") (name "/OUT2B_1") (class "Default")
      (node (ref "OUT2B_1") (pin "1") (pinfunction "1_1") (pintype "passive"))
      (node (ref "U1") (pin "1") (pinfunction "OUT2B_1") (pintype "passive"))
    )
    (net (code "28") (name "/OUT2B_2") (class "Default")
      (node (ref "OUT2B_2") (pin "1") (pinfunction "1_1") (pintype "passive"))
      (node (ref "U2") (pin "1") (pinfunction "OUT2B_1") (pintype "passive"))
    )
    (net (code "29") (name "/RESET_1") (class "Default")
      (node (ref "R31") (pin "1") (pinfunction "1_1") (pintype "passive"))
      (node (ref "U1") (pin "12") (pinfunction "~{RESET}_12") (pintype "passive"))
      (node (ref "U3") (pin "27") (pinfunction "IO16_27") (pintype "bidirectional"))
    )
    (net (code "30") (name "/RESET_2") (class "Default")
      (node (ref "R32") (pin "1") (pinfunction "1_1") (pintype "passive"))
      (node (ref "U2") (pin "12") (pinfunction "~{RESET}_12") (pintype "passive"))
      (node (ref "U3") (pin "31") (pinfunction "IO19_31") (pintype "bidirectional"))
    )
    (net (code "31") (name "/SLEEP_1") (class "Default")
      (node (ref "R21") (pin "1") (pinfunction "1_1") (pintype "passive"))
      (node (ref "U1") (pin "14") (pinfunction "~{SLEEP}_14") (pintype "passive"))
      (node (ref "U3") (pin "28") (pinfunction "IO17_28") (pintype "bidirectional"))
    )
    (net (code "32") (name "/SLEEP_2") (class "Default")
      (node (ref "R22") (pin "1") (pinfunction "1_1") (pintype "passive"))
      (node (ref "U2") (pin "14") (pinfunction "~{SLEEP}_14") (pintype "passive"))
      (node (ref "U3") (pin "16") (pinfunction "IO13_16") (pintype "bidirectional"))
    )
    (net (code "33") (name "/STEP_1") (class "Default")
      (node (ref "R15") (pin "1") (pinfunction "1_1") (pintype "passive"))
      (node (ref "U1") (pin "16") (pinfunction "STEP_16") (pintype "passive"))
      (node (ref "U3") (pin "29") (pinfunction "IO5_29") (pintype "bidirectional"))
    )
    (net (code "34") (name "/STEP_2") (class "Default")
      (node (ref "R17") (pin "1") (pinfunction "1_1") (pintype "passive"))
      (node (ref "U2") (pin "16") (pinfunction "STEP_16") (pintype "passive"))
      (node (ref "U3") (pin "12") (pinfunction "IO27_12") (pintype "bidirectional"))
    )
    (net (code "35") (name "3.3V") (class "Default")
      (node (ref "C11") (pin "2") (pinfunction "2_2") (pintype "passive"))
      (node (ref "C12") (pin "2") (pinfunction "2_2") (pintype "passive"))
      (node (ref "C15") (pin "1") (pinfunction "1_1") (pintype "passive"))
      (node (ref "C16") (pin "1") (pinfunction "1_1") (pintype "passive"))
      (node (ref "C17") (pin "2") (pinfunction "2_2") (pintype "passive"))
      (node (ref "C18") (pin "1") (pinfunction "1_1") (pintype "passive"))
      (node (ref "C20") (pin "2") (pinfunction "2_2") (pintype "passive"))
      (node (ref "C21") (pin "1") (pinfunction "1_1") (pintype "passive"))
      (node (ref "C22") (pin "1") (pinfunction "1_1") (pintype "passive"))
      (node (ref "C23") (pin "1") (pinfunction "1_1") (pintype "passive"))
      (node (ref "C32") (pin "2") (pinfunction "2_2") (pintype "passive"))
      (node (ref "J3") (pin "1") (pinfunction "1_1") (pintype "passive"))
      (node (ref "J4") (pin "1") (pinfunction "1_1") (pintype "passive"))
      (node (ref "J5") (pin "1") (pinfunction "1_1") (pintype "passive"))
      (node (ref "R10") (pin "2") (pinfunction "2_2") (pintype "passive"))
      (node (ref "R11") (pin "2") (pinfunction "2_2") (pintype "passive"))
      (node (ref "R12") (pin "2") (pinfunction "2_2") (pintype "passive"))
      (node (ref "R15") (pin "2") (pinfunction "2_2") (pintype "passive"))
      (node (ref "R17") (pin "2") (pinfunction "2_2") (pintype "passive"))
      (node (ref "R21") (pin "2") (pinfunction "2_2") (pintype "passive"))
      (node (ref "R22") (pin "2") (pinfunction "2_2") (pintype "passive"))
      (node (ref "R23") (pin "2") (pinfunction "2_2") (pintype "passive"))
      (node (ref "R24") (pin "2") (pinfunction "2_2") (pintype "passive"))
      (node (ref "R25") (pin "1") (pinfunction "1_1") (pintype "passive"))
      (node (ref "R26") (pin "1") (pinfunction "1_1") (pintype "passive"))
      (node (ref "R27") (pin "2") (pinfunction "2_2") (pintype "passive"))
      (node (ref "R28") (pin "2") (pinfunction "2_2") (pintype "passive"))
      (node (ref "R29") (pin "2") (pinfunction "2_2") (pintype "passive"))
      (node (ref "R30") (pin "2") (pinfunction "2_2") (pintype "passive"))
      (node (ref "R31") (pin "2") (pinfunction "2_2") (pintype "passive"))
      (node (ref "R32") (pin "2") (pinfunction "2_2") (pintype "passive"))
      (node (ref "R33") (pin "2") (pinfunction "2_2") (pintype "passive"))
      (node (ref "R34") (pin "1") (pinfunction "1_1") (pintype "passive"))
      (node (ref "R45") (pin "2") (pinfunction "2_2") (pintype "passive"))
      (node (ref "R46") (pin "2") (pinfunction "2_2") (pintype "passive"))
      (node (ref "R9") (pin "2") (pinfunction "2_2") (pintype "passive"))
      (node (ref "U1") (pin "15") (pinfunction "VDD_15") (pintype "passive"))
      (node (ref "U2") (pin "15") (pinfunction "VDD_15") (pintype "passive"))
      (node (ref "U3") (pin "2") (pinfunction "3V3_2") (pintype "power_in"))
      (node (ref "U4") (pin "1") (pinfunction "CPVDD_1") (pintype "power_in"))
      (node (ref "U4") (pin "20") (pinfunction "DVDD_20") (pintype "power_in"))
      (node (ref "U4") (pin "8") (pinfunction "AVDD_8") (pintype "power_in"))
      (node (ref "U5") (pin "5") (pinfunction "VOUT_5") (pintype "passive"))
    )
    (net (code "36") (name "5V") (class "Default")
      (node (ref "C1") (pin "1") (pinfunction "1_1") (pintype "passive"))
      (node (ref "C2") (pin "1") (pinfunction "1_1") (pintype "passive"))
      (node (ref "C29") (pin "1") (pinfunction "1_1") (pintype "passive"))
      (node (ref "C33") (pin "2") (pinfunction "2_2") (pintype "passive"))
      (node (ref "D1") (pin "K") (pinfunction "K_K") (pintype "passive"))
      (node (ref "D2") (pin "K") (pinfunction "K_K") (pintype "passive"))
      (node (ref "D3") (pin "1") (pinfunction "A_1") (pintype "passive"))
      (node (ref "J1") (pin "1") (pinfunction "1_1") (pintype "passive"))
      (node (ref "J2") (pin "1") (pinfunction "1_1") (pintype "passive"))
      (node (ref "L1") (pin "2") (pinfunction "2_2") (pintype "passive"))
      (node (ref "R43") (pin "1") (pinfunction "1_1") (pintype "passive"))
      (node (ref "U5") (pin "1") (pinfunction "VIN_1") (pintype "passive"))
      (node (ref "U5") (pin "3") (pinfunction "CE_3") (pintype "passive"))
    )
    (net (code "37") (name "GND") (class "Default")
      (node (ref "C11") (pin "1") (pinfunction "1_1") (pintype "passive"))
      (node (ref "C12") (pin "1") (pinfunction "1_1") (pintype "passive"))
      (node (ref "C13") (pin "1") (pinfunction "1_1") (pintype "passive"))
      (node (ref "C14") (pin "1") (pinfunction "1_1") (pintype "passive"))
      (node (ref "C15") (pin "2") (pinfunction "2_2") (pintype "passive"))
      (node (ref "C16") (pin "2") (pinfunction "2_2") (pintype "passive"))
      (node (ref "C17") (pin "1") (pinfunction "1_1") (pintype "passive"))
      (node (ref "C18") (pin "2") (pinfunction "2_2") (pintype "passive"))
      (node (ref "C19") (pin "2") (pinfunction "2_2") (pintype "passive"))
      (node (ref "C20") (pin "1") (pinfunction "1_1") (pintype "passive"))
      (node (ref "C21") (pin "2") (pinfunction "2_2") (pintype "passive"))
      (node (ref "C22") (pin "2") (pinfunction "2_2") (pintype "passive"))
      (node (ref "C23") (pin "2") (pinfunction "2_2") (pintype "passive"))
      (node (ref "C24") (pin "1") (pinfunction "1_1") (pintype "passive"))
      (node (ref "C25") (pin "2") (pinfunction "2_2") (pintype "passive"))
      (node (ref "C26") (pin "2") (pinfunction "2_2") (pintype "passive"))
      (node (ref "C27") (pin "2") (pinfunction "2_2") (pintype "passive"))
      (node (ref "C29") (pin "2") (pinfunction "2_2") (pintype "passive"))
      (node (ref "C3") (pin "1") (pinfunction "1_1") (pintype "passive"))
      (node (ref "C31") (pin "2") (pinfunction "2_2") (pintype "passive"))
      (node (ref "C32") (pin "1") (pinfunction "1_1") (pintype "passive"))
      (node (ref "C33") (pin "1") (pinfunction "1_1") (pintype "passive"))
      (node (ref "C35") (pin "1") (pinfunction "1_1") (pintype "passive"))
      (node (ref "C36") (pin "2") (pinfunction "2_2") (pintype "passive"))
      (node (ref "C4") (pin "1") (pinfunction "1_1") (pintype "passive"))
      (node (ref "C5") (pin "1") (pinfunction "1_1") (pintype "passive"))
      (node (ref "C6") (pin "1") (pinfunction "1_1") (pintype "passive"))
      (node (ref "J3") (pin "2") (pinfunction "2_2") (pintype "passive"))
      (node (ref "J4") (pin "2") (pinfunction "2_2") (pintype "passive"))
      (node (ref "J5") (pin "4") (pinfunction "4_4") (pintype "passive"))
      (node (ref "J6") (pin "1") (pinfunction "SLEEVE_1") (pintype "passive"))
      (node (ref "J7") (pin "2") (pinfunction "2_2") (pintype "passive"))
      (node (ref "J7") (pin "3") (pinfunction "3_3") (pintype "passive"))
      (node (ref "J8") (pin "2") (pinfunction "2_2") (pintype "passive"))
      (node (ref "Q1") (pin "2") (pinfunction "S_2") (pintype "passive"))
      (node (ref "Q2") (pin "2") (pinfunction "S_2") (pintype "passive"))
      (node (ref "R1") (pin "2") (pinfunction "2_2") (pintype "passive"))
      (node (ref "R13") (pin "1") (pinfunction "1_1") (pintype "passive"))
      (node (ref "R14") (pin "1") (pinfunction "1_1") (pintype "passive"))
      (node (ref "R16") (pin "2") (pinfunction "TAP_2") (pintype "passive"))
      (node (ref "R16") (pin "3") (pinfunction "BOT_3") (pintype "passive"))
      (node (ref "R18") (pin "2") (pinfunction "TAP_2") (pintype "passive"))
      (node (ref "R18") (pin "3") (pinfunction "BOT_3") (pintype "passive"))
      (node (ref "R19") (pin "1") (pinfunction "1_1") (pintype "passive"))
      (node (ref "R2") (pin "2") (pinfunction "2_2") (pintype "passive"))
      (node (ref "R20") (pin "1") (pinfunction "1_1") (pintype "passive"))
      (node (ref "R3") (pin "2") (pinfunction "2_2") (pintype "passive"))
      (node (ref "R4") (pin "2") (pinfunction "2_2") (pintype "passive"))
      (node (ref "R40") (pin "1") (pinfunction "1_1") (pintype "passive"))
      (node (ref "R42") (pin "2") (pinfunction "2_2") (pintype "passive"))
      (node (ref "R44") (pin "2") (pinfunction "2_2") (pintype "passive"))
      (node (ref "R7") (pin "2") (pinfunction "2_2") (pintype "passive"))
      (node (ref "R8") (pin "2") (pinfunction "2_2") (pintype "passive"))
      (node (ref "SW1") (pin "2") (pinfunction "2_2") (pintype "passive"))
      (node (ref "SW2") (pin "1") (pinfunction "1_1") (pintype "passive"))
      (node (ref "SW3") (pin "1") (pinfunction "1_1") (pintype "passive"))
      (node (ref "U1") (pin "18") (pinfunction "GND_18") (pintype "passive"))
      (node (ref "U1") (pin "29") (pinfunction "PAD_29") (pintype "passive"))
      (node (ref "U1") (pin "3") (pinfunction "GND_3") (pintype "passive"))
      (node (ref "U2") (pin "18") (pinfunction "GND_18") (pintype "passive"))
      (node (ref "U2") (pin "29") (pinfunction "PAD_29") (pintype "passive"))
      (node (ref "U2") (pin "3") (pinfunction "GND_3") (pintype "passive"))
      (node (ref "U3") (pin "1") (pinfunction "GND_1") (pintype "power_in"))
      (node (ref "U3") (pin "15") (pinfunction "GND_15") (pintype "power_in"))
      (node (ref "U3") (pin "38") (pinfunction "GND_38") (pintype "power_in"))
      (node (ref "U3") (pin "39") (pinfunction "GND_39") (pintype "power_in"))
      (node (ref "U4") (pin "10") (pinfunction "DEMP_10") (pintype "input"))
      (node (ref "U4") (pin "11") (pinfunction "FLT_11") (pintype "input"))
      (node (ref "U4") (pin "12") (pinfunction "SCK_12") (pintype "input"))
      (node (ref "U4") (pin "16") (pinfunction "FMT_16") (pintype "input"))
      (node (ref "U4") (pin "19") (pinfunction "DGND_19") (pintype "power_in"))
      (node (ref "U4") (pin "3") (pinfunction "CPGND_3") (pintype "power_in"))
      (node (ref "U4") (pin "9") (pinfunction "AGND_9") (pintype "power_in"))
      (node (ref "U5") (pin "2") (pinfunction "GND_2") (pintype "passive"))
      (node (ref "U6") (pin "0") (pinfunction "EP_0") (pintype "passive"))
      (node (ref "U6") (pin "4") (pinfunction "GND_4") (pintype "passive"))
    )
    (net (code "38") (name "Net-(C34-Pad2)") (class "Default")
      (node (ref "C34") (pin "2") (pinfunction "2_2") (pintype "passive"))
      (node (ref "R42") (pin "1") (pinfunction "1_1") (pintype "passive"))
    )
    (net (code "39") (name "Net-(D3-K)") (class "Default")
      (node (ref "D3") (pin "2") (pinfunction "K_2") (pintype "passive"))
      (node (ref "R40") (pin "2") (pinfunction "2_2") (pintype "passive"))
    )
    (net (code "40") (name "Net-(D4-PadA)") (class "Default")
      (node (ref "D4") (pin "A") (pinfunction "A_A") (pintype "passive"))
      (node (ref "J7") (pin "1") (pinfunction "1_1") (pintype "passive"))
      (node (ref "J8") (pin "1") (pinfunction "1_1") (pintype "passive"))
    )
    (net (code "41") (name "Net-(J6-RING)") (class "Default")
      (node (ref "C25") (pin "1") (pinfunction "1_1") (pintype "passive"))
      (node (ref "J6") (pin "3") (pinfunction "RING_3") (pintype "passive"))
      (node (ref "R36") (pin "2") (pinfunction "2_2") (pintype "passive"))
    )
    (net (code "42") (name "Net-(J6-TIP)") (class "Default")
      (node (ref "C26") (pin "1") (pinfunction "1_1") (pintype "passive"))
      (node (ref "J6") (pin "2") (pinfunction "TIP_2") (pintype "passive"))
      (node (ref "R38") (pin "2") (pinfunction "2_2") (pintype "passive"))
    )
    (net (code "43") (name "Net-(Q1-D)") (class "Default")
      (node (ref "C1") (pin "2") (pinfunction "2_2") (pintype "passive"))
      (node (ref "D1") (pin "A") (pinfunction "A_A") (pintype "passive"))
      (node (ref "J1") (pin "2") (pinfunction "2_2") (pintype "passive"))
      (node (ref "Q1") (pin "3") (pinfunction "D_3") (pintype "passive"))
    )
    (net (code "44") (name "Net-(Q1-G)") (class "Default")
      (node (ref "Q1") (pin "1") (pinfunction "G_1") (pintype "passive"))
      (node (ref "R5") (pin "2") (pinfunction "2_2") (pintype "passive"))
    )
    (net (code "45") (name "Net-(Q2-D)") (class "Default")
      (node (ref "C2") (pin "2") (pinfunction "2_2") (pintype "passive"))
      (node (ref "D2") (pin "A") (pinfunction "A_A") (pintype "passive"))
      (node (ref "J2") (pin "2") (pinfunction "2_2") (pintype "passive"))
      (node (ref "Q2") (pin "3") (pinfunction "D_3") (pintype "passive"))
    )
    (net (code "46") (name "Net-(Q2-G)") (class "Default")
      (node (ref "Q2") (pin "1") (pinfunction "G_1") (pintype "passive"))
      (node (ref "R6") (pin "2") (pinfunction "2_2") (pintype "passive"))
    )
    (net (code "47") (name "Net-(R16-TOP)") (class "Default")
      (node (ref "R10") (pin "1") (pinfunction "1_1") (pintype "passive"))
      (node (ref "R16") (pin "1") (pinfunction "TOP_1") (pintype "passive"))
      (node (ref "U1") (pin "17") (pinfunction "REF_17") (pintype "passive"))
    )
    (net (code "48") (name "Net-(R18-TOP)") (class "Default")
      (node (ref "R12") (pin "1") (pinfunction "1_1") (pintype "passive"))
      (node (ref "R18") (pin "1") (pinfunction "TOP_1") (pintype "passive"))
      (node (ref "U2") (pin "17") (pinfunction "REF_17") (pintype "passive"))
    )
    (net (code "49") (name "Net-(U1-CP1)") (class "Default")
      (node (ref "C7") (pin "1") (pinfunction "1_1") (pintype "passive"))
      (node (ref "U1") (pin "4") (pinfunction "CP1_4") (pintype "passive"))
    )
    (net (code "50") (name "Net-(U1-CP2)") (class "Default")
      (node (ref "C7") (pin "2") (pinfunction "2_2") (pintype "passive"))
      (node (ref "U1") (pin "5") (pinfunction "CP2_5") (pintype "passive"))
    )
    (net (code "51") (name "Net-(U1-ROSC)") (class "Default")
      (node (ref "R19") (pin "2") (pinfunction "2_2") (pintype "passive"))
      (node (ref "U1") (pin "13") (pinfunction "ROSC_13") (pintype "passive"))
    )
    (net (code "52") (name "Net-(U1-SENSE1)") (class "Default")
      (node (ref "R3") (pin "1") (pinfunction "1_1") (pintype "passive"))
      (node (ref "U1") (pin "23") (pinfunction "SENSE1_23") (pintype "passive"))
    )
    (net (code "53") (name "Net-(U1-SENSE2)") (class "Default")
      (node (ref "R1") (pin "1") (pinfunction "1_1") (pintype "passive"))
      (node (ref "U1") (pin "27") (pinfunction "SENSE2_27") (pintype "passive"))
    )
    (net (code "54") (name "Net-(U1-VCP)") (class "Default")
      (node (ref "C9") (pin "1") (pinfunction "1_1") (pintype "passive"))
      (node (ref "U1") (pin "6") (pinfunction "VCP_6") (pintype "passive"))
    )
    (net (code "55") (name "Net-(U1-VREG)") (class "Default")
      (node (ref "C13") (pin "2") (pinfunction "2_2") (pintype "passive"))
      (node (ref "U1") (pin "8") (pinfunction "VREG_8") (pintype "passive"))
    )
    (net (code "56") (name "Net-(U2-CP1)") (class "Default")
      (node (ref "C8") (pin "1") (pinfunction "1_1") (pintype "passive"))
      (node (ref "U2") (pin "4") (pinfunction "CP1_4") (pintype "passive"))
    )
    (net (code "57") (name "Net-(U2-CP2)") (class "Default")
      (node (ref "C8") (pin "2") (pinfunction "2_2") (pintype "passive"))
      (node (ref "U2") (pin "5") (pinfunction "CP2_5") (pintype "passive"))
    )
    (net (code "58") (name "Net-(U2-ROSC)") (class "Default")
      (node (ref "R20") (pin "2") (pinfunction "2_2") (pintype "passive"))
      (node (ref "U2") (pin "13") (pinfunction "ROSC_13") (pintype "passive"))
    )
    (net (code "59") (name "Net-(U2-SENSE1)") (class "Default")
      (node (ref "R4") (pin "1") (pinfunction "1_1") (pintype "passive"))
      (node (ref "U2") (pin "23") (pinfunction "SENSE1_23") (pintype "passive"))
    )
    (net (code "60") (name "Net-(U2-SENSE2)") (class "Default")
      (node (ref "R2") (pin "1") (pinfunction "1_1") (pintype "passive"))
      (node (ref "U2") (pin "27") (pinfunction "SENSE2_27") (pintype "passive"))
    )
    (net (code "61") (name "Net-(U2-VCP)") (class "Default")
      (node (ref "C10") (pin "1") (pinfunction "1_1") (pintype "passive"))
      (node (ref "U2") (pin "6") (pinfunction "VCP_6") (pintype "passive"))
    )
    (net (code "62") (name "Net-(U2-VREG)") (class "Default")
      (node (ref "C14") (pin "2") (pinfunction "2_2") (pintype "passive"))
      (node (ref "U2") (pin "8") (pinfunction "VREG_8") (pintype "passive"))
    )
    (net (code "63") (name "Net-(U3-EN)") (class "Default")
      (node (ref "C19") (pin "1") (pinfunction "1_1") (pintype "passive"))
      (node (ref "R34") (pin "2") (pinfunction "2_2") (pintype "passive"))
      (node (ref "U3") (pin "3") (pinfunction "EN_3") (pintype "input"))
    )
    (net (code "64") (name "Net-(U3-IO0)") (class "Default")
      (node (ref "R33") (pin "1") (pinfunction "1_1") (pintype "passive"))
      (node (ref "SW1") (pin "1") (pinfunction "1_1") (pintype "passive"))
      (node (ref "U3") (pin "25") (pinfunction "IO0_25") (pintype "bidirectional"))
    )
    (net (code "65") (name "Net-(U3-RXD0)") (class "Default")
      (node (ref "J5") (pin "3") (pinfunction "3_3") (pintype "passive"))
      (node (ref "U3") (pin "34") (pinfunction "RXD0_34") (pintype "bidirectional"))
    )
    (net (code "66") (name "Net-(U3-TXD0)") (class "Default")
      (node (ref "J5") (pin "2") (pinfunction "2_2") (pintype "passive"))
      (node (ref "U3") (pin "35") (pinfunction "TXD0_35") (pintype "bidirectional"))
    )
    (net (code "67") (name "Net-(U4-BCK)") (class "Default")
      (node (ref "R37") (pin "2") (pinfunction "2_2") (pintype "passive"))
      (node (ref "U4") (pin "13") (pinfunction "BCK_13") (pintype "input"))
    )
    (net (code "68") (name "Net-(U4-CAPM)") (class "Default")
      (node (ref "C28") (pin "1") (pinfunction "1_1") (pintype "passive"))
      (node (ref "U4") (pin "4") (pinfunction "CAPM_4") (pintype "passive"))
    )
    (net (code "69") (name "Net-(U4-CAPP)") (class "Default")
      (node (ref "C28") (pin "2") (pinfunction "2_2") (pintype "passive"))
      (node (ref "U4") (pin "2") (pinfunction "CAPP_2") (pintype "passive"))
    )
    (net (code "70") (name "Net-(U4-DIN)") (class "Default")
      (node (ref "R35") (pin "2") (pinfunction "2_2") (pintype "passive"))
      (node (ref "U4") (pin "14") (pinfunction "DIN_14") (pintype "input"))
    )
    (net (code "71") (name "Net-(U4-LDOO)") (class "Default")
      (node (ref "C24") (pin "2") (pinfunction "2_2") (pintype "passive"))
      (node (ref "U4") (pin "18") (pinfunction "LDOO_18") (pintype "power_in"))
    )
    (net (code "72") (name "Net-(U4-LRCK)") (class "Default")
      (node (ref "R39") (pin "2") (pinfunction "2_2") (pintype "passive"))
      (node (ref "U4") (pin "15") (pinfunction "LRCK_15") (pintype "input"))
    )
    (net (code "73") (name "Net-(U4-OUTL)") (class "Default")
      (node (ref "R36") (pin "1") (pinfunction "1_1") (pintype "passive"))
      (node (ref "U4") (pin "6") (pinfunction "OUTL_6") (pintype "output"))
    )
    (net (code "74") (name "Net-(U4-OUTR)") (class "Default")
      (node (ref "R38") (pin "1") (pinfunction "1_1") (pintype "passive"))
      (node (ref "U4") (pin "7") (pinfunction "OUTR_7") (pintype "output"))
    )
    (net (code "75") (name "Net-(U4-VNEG)") (class "Default")
      (node (ref "C27") (pin "1") (pinfunction "1_1") (pintype "passive"))
      (node (ref "U4") (pin "5") (pinfunction "VNEG_5") (pintype "output"))
    )
    (net (code "76") (name "Net-(U6-BS)") (class "Default")
      (node (ref "C30") (pin "1") (pinfunction "1_1") (pintype "passive"))
      (node (ref "U6") (pin "1") (pinfunction "BS_1") (pintype "passive"))
    )
    (net (code "77") (name "Net-(U6-COMP)") (class "Default")
      (node (ref "C34") (pin "1") (pinfunction "1_1") (pintype "passive"))
      (node (ref "U6") (pin "6") (pinfunction "COMP_6") (pintype "passive"))
    )
    (net (code "78") (name "Net-(U6-EN)") (class "Default")
      (node (ref "R41") (pin "1") (pinfunction "1_1") (pintype "passive"))
      (node (ref "U6") (pin "7") (pinfunction "EN_7") (pintype "passive"))
    )
    (net (code "79") (name "Net-(U6-FB)") (class "Default")
      (node (ref "R43") (pin "2") (pinfunction "2_2") (pintype "passive"))
      (node (ref "R44") (pin "1") (pinfunction "1_1") (pintype "passive"))
      (node (ref "U6") (pin "5") (pinfunction "FB_5") (pintype "passive"))
    )
    (net (code "80") (name "Net-(U6-SS)") (class "Default")
      (node (ref "C31") (pin "1") (pinfunction "1_1") (pintype "passive"))
      (node (ref "U6") (pin "8") (pinfunction "SS_8") (pintype "passive"))
    )
    (net (code "81") (name "Net-(U6-SW)") (class "Default")
      (node (ref "C30") (pin "2") (pinfunction "2_2") (pintype "passive"))
      (node (ref "L1") (pin "1") (pinfunction "1_1") (pintype "passive"))
      (node (ref "U6") (pin "3") (pinfunction "SW_3") (pintype "passive"))
    )
    (net (code "82") (name "VIN") (class "Default")
      (node (ref "C10") (pin "2") (pinfunction "2_2") (pintype "passive"))
      (node (ref "C3") (pin "2") (pinfunction "2_2") (pintype "passive"))
      (node (ref "C35") (pin "2") (pinfunction "2_2") (pintype "passive"))
      (node (ref "C36") (pin "1") (pinfunction "1_1") (pintype "passive"))
      (node (ref "C4") (pin "2") (pinfunction "2_2") (pintype "passive"))
      (node (ref "C5") (pin "2") (pinfunction "2_2") (pintype "passive"))
      (node (ref "C6") (pin "2") (pinfunction "2_2") (pintype "passive"))
      (node (ref "C9") (pin "2") (pinfunction "2_2") (pintype "passive"))
      (node (ref "D4") (pin "K") (pinfunction "K_K") (pintype "passive"))
      (node (ref "R41") (pin "2") (pinfunction "2_2") (pintype "passive"))
      (node (ref "U1") (pin "22") (pinfunction "VBB1_22") (pintype "passive"))
      (node (ref "U1") (pin "28") (pinfunction "VBB2_28") (pintype "passive"))
      (node (ref "U2") (pin "22") (pinfunction "VBB1_22") (pintype "passive"))
      (node (ref "U2") (pin "28") (pinfunction "VBB2_28") (pintype "passive"))
      (node (ref "U6") (pin "2") (pinfunction "IN_2") (pintype "passive"))
    )
    (net (code "83") (name "unconnected-(J6-TIP_SWITCH-Pad10)") (class "Default")
      (node (ref "J6") (pin "10") (pinfunction "TIP_SWITCH_10") (pintype "passive"))
    )
    (net (code "84") (name "unconnected-(U1-NC-Pad7)") (class "Default")
      (node (ref "U1") (pin "7") (pinfunction "NC_7") (pintype "passive"))
    )
    (net (code "85") (name "unconnected-(U1-NC-Pad20)") (class "Default")
      (node (ref "U1") (pin "20") (pinfunction "NC_20") (pintype "passive"))
    )
    (net (code "86") (name "unconnected-(U1-NC-Pad25)") (class "Default")
      (node (ref "U1") (pin "25") (pinfunction "NC_25") (pintype "passive"))
    )
    (net (code "87") (name "unconnected-(U2-NC-Pad7)") (class "Default")
      (node (ref "U2") (pin "7") (pinfunction "NC_7") (pintype "passive"))
    )
    (net (code "88") (name "unconnected-(U2-NC-Pad20)") (class "Default")
      (node (ref "U2") (pin "20") (pinfunction "NC_20") (pintype "passive"))
    )
    (net (code "89") (name "unconnected-(U2-NC-Pad25)") (class "Default")
      (node (ref "U2") (pin "25") (pinfunction "NC_25") (pintype "passive"))
    )
    (net (code "90") (name "unconnected-(U3-IO12-Pad14)") (class "Default")
      (node (ref "U3") (pin "14") (pinfunction "IO12_14") (pintype "bidirectional"))
    )
    (net (code "91") (name "unconnected-(U3-IO21-Pad33)") (class "Default")
      (node (ref "U3") (pin "33") (pinfunction "IO21_33") (pintype "bidirectional"))
    )
    (net (code "92") (name "unconnected-(U3-IO34-Pad6)") (class "Default")
      (node (ref "U3") (pin "6") (pinfunction "IO34_6") (pintype "input"))
    )
    (net (code "93") (name "unconnected-(U3-IO35-Pad7)") (class "Default")
      (node (ref "U3") (pin "7") (pinfunction "IO35_7") (pintype "input"))
    )
    (net (code "94") (name "unconnected-(U3-SCK{slash}CLK-Pad20)") (class "Default")
      (node (ref "U3") (pin "20") (pinfunction "SCK/CLK_20") (pintype "bidirectional"))
    )
    (net (code "95") (name "unconnected-(U3-SCS{slash}CMD-Pad19)") (class "Default")
      (node (ref "U3") (pin "19") (pinfunction "SCS/CMD_19") (pintype "bidirectional"))
    )
    (net (code "96") (name "unconnected-(U3-SDI{slash}SD1-Pad22)") (class "Default")
      (node (ref "U3") (pin "22") (pinfunction "SDI/SD1_22") (pintype "bidirectional"))
    )
    (net (code "97") (name "unconnected-(U3-SDO{slash}SD0-Pad21)") (class "Default")
      (node (ref "U3") (pin "21") (pinfunction "SDO/SD0_21") (pintype "bidirectional"))
    )
    (net (code "98") (name "unconnected-(U3-SENSOR_VN-Pad5)") (class "Default")
      (node (ref "U3") (pin "5") (pinfunction "SENSOR_VN_5") (pintype "input"))
    )
    (net (code "99") (name "unconnected-(U3-SENSOR_VP-Pad4)") (class "Default")
      (node (ref "U3") (pin "4") (pinfunction "SENSOR_VP_4") (pintype "input"))
    )
    (net (code "100") (name "unconnected-(U3-SHD{slash}SD2-Pad17)") (class "Default")
      (node (ref "U3") (pin "17") (pinfunction "SHD/SD2_17") (pintype "bidirectional"))
    )
    (net (code "101") (name "unconnected-(U3-SWP{slash}SD3-Pad18)") (class "Default")
      (node (ref "U3") (pin "18") (pinfunction "SWP/SD3_18") (pintype "bidirectional"))
    )
    (net (code "102") (name "unconnected-(U5-NC-Pad4)") (class "Default")
      (node (ref "U5") (pin "4") (pinfunction "NC_4") (pintype "passive"))
    )
  )
)
